# PCB-BI8-3x5C3_V2.net
KiCad netlist of a schematic drawn in EAGLE
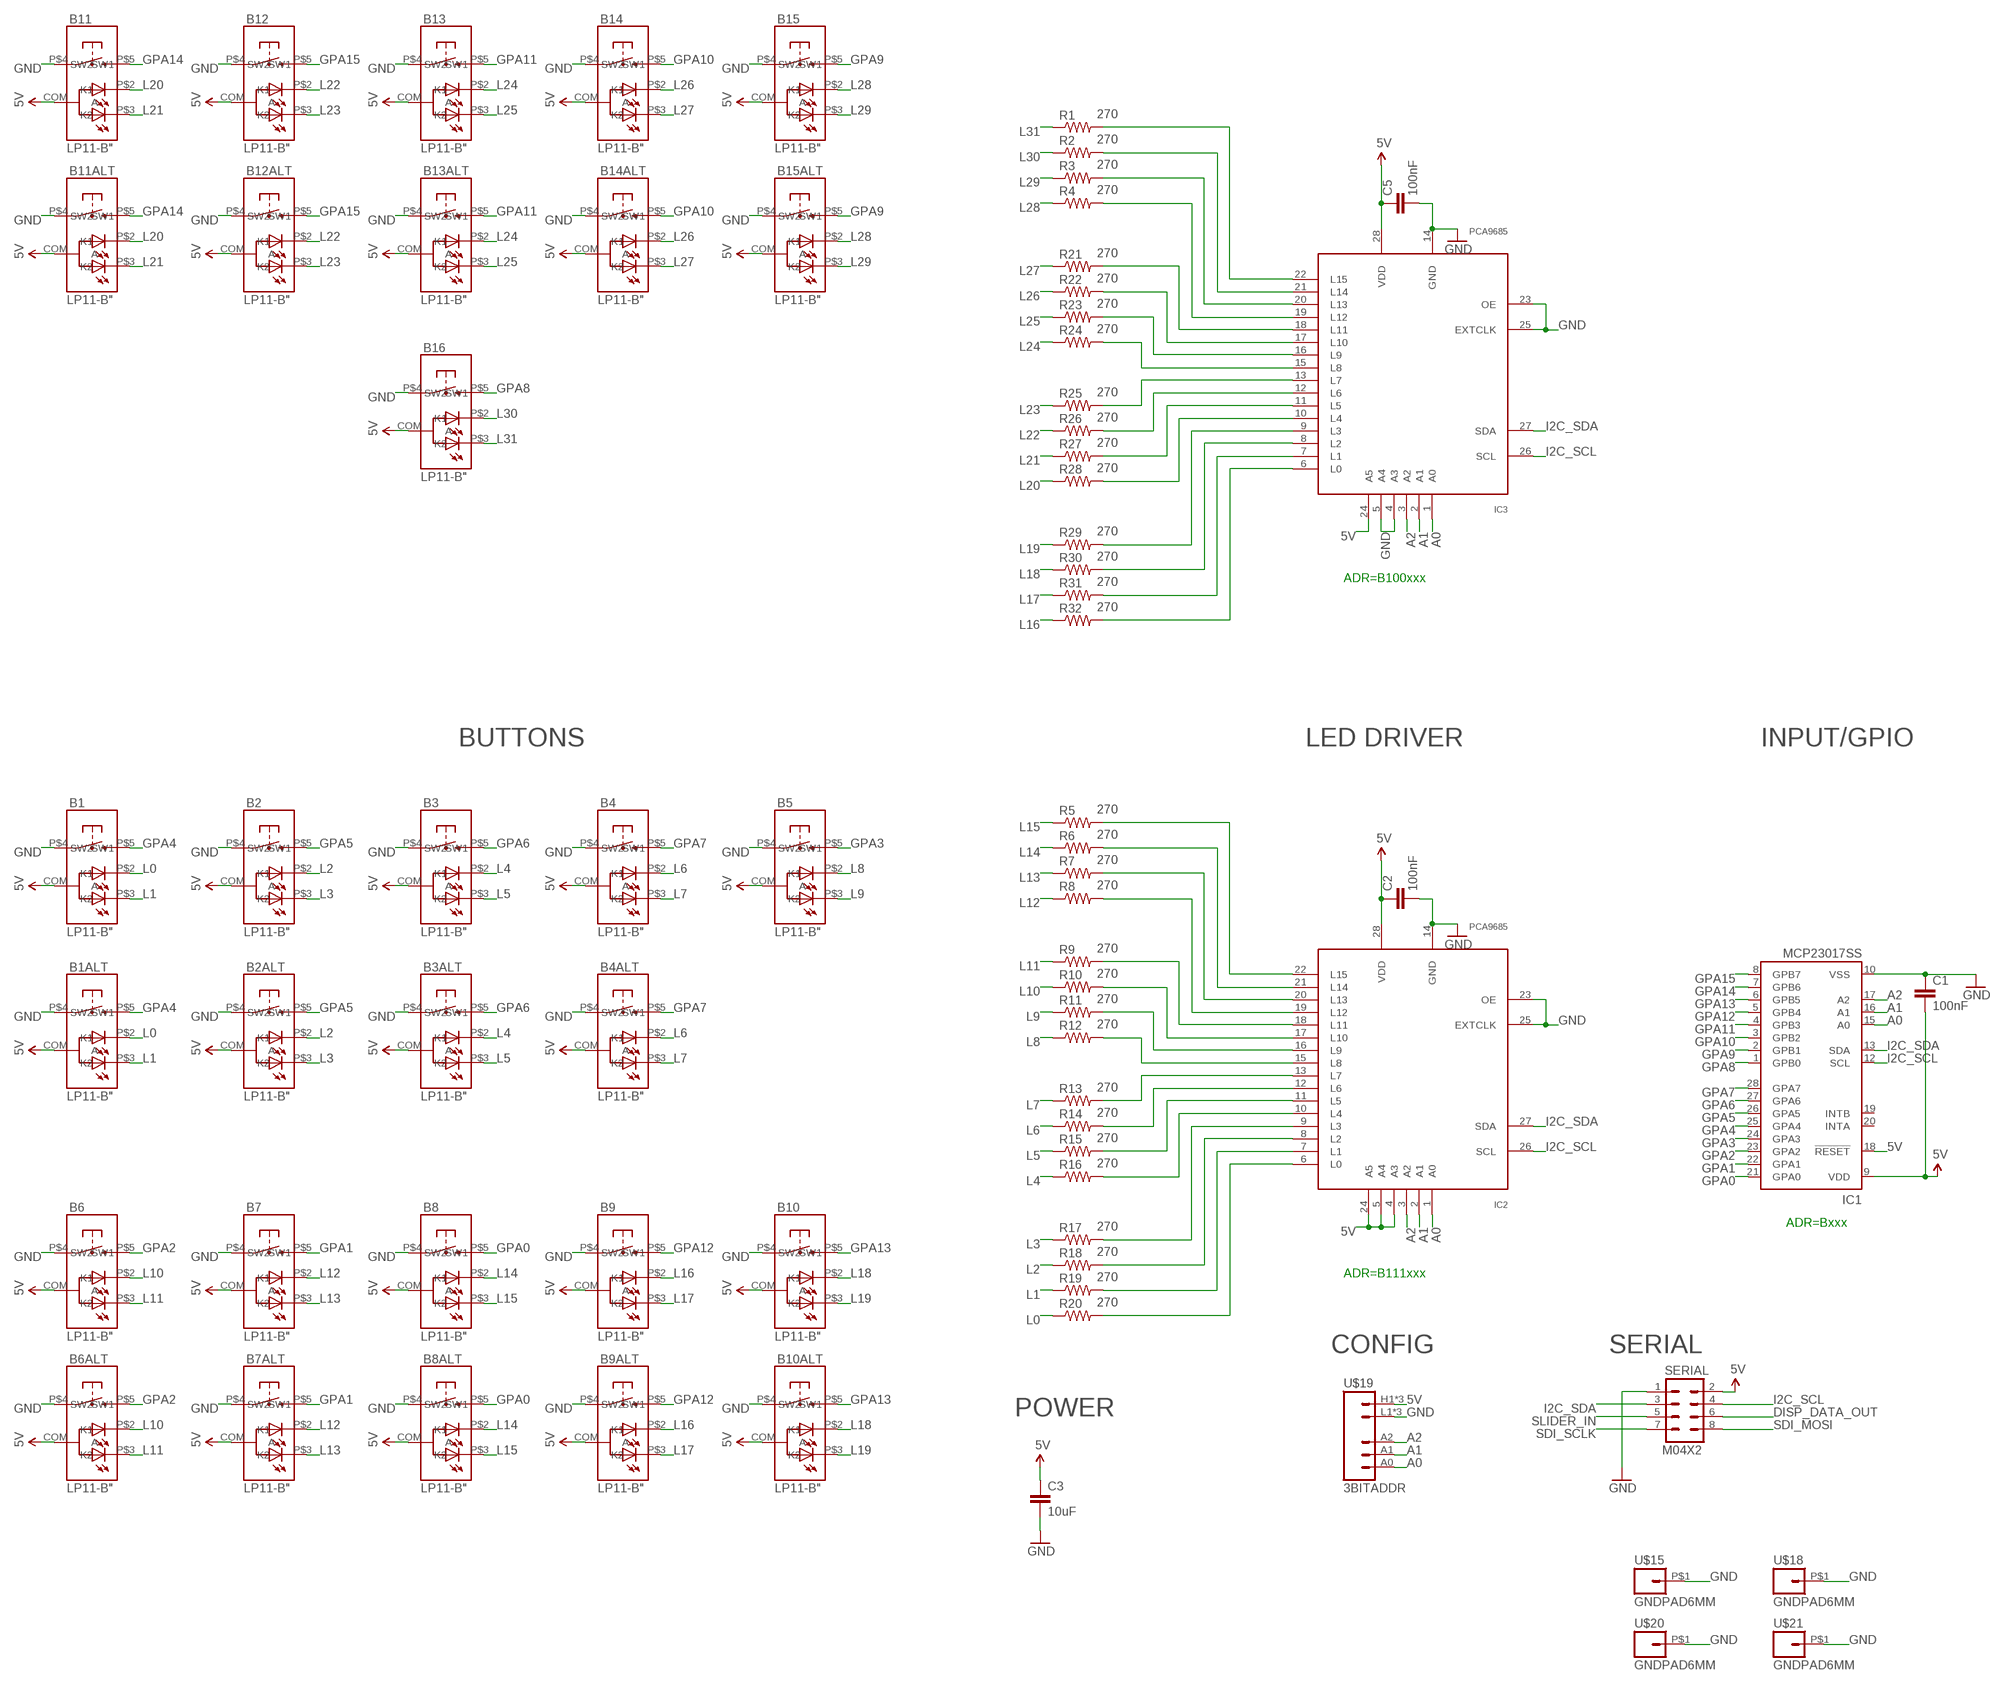
[diagram p0: schematic, sheet 1]

(export (version "E")
  (design (tool "Eeschema 10.0.6"))
  (components
    (comp (ref "B1")
      (value "LP11-B\"")
      (footprint "eagle-import:LP11")
      (libsource (lib "eagle-import") (part "LP11-B{dblquote}"))
    )
    (comp (ref "B1ALT")
      (value "LP11-B\"")
      (footprint "eagle-import:LP11")
      (libsource (lib "eagle-import") (part "LP11-B{dblquote}"))
    )
    (comp (ref "B2")
      (value "LP11-B\"")
      (footprint "eagle-import:LP11")
      (libsource (lib "eagle-import") (part "LP11-B{dblquote}"))
    )
    (comp (ref "B2ALT")
      (value "LP11-B\"")
      (footprint "eagle-import:LP11")
      (libsource (lib "eagle-import") (part "LP11-B{dblquote}"))
    )
    (comp (ref "B3")
      (value "LP11-B\"")
      (footprint "eagle-import:LP11")
      (libsource (lib "eagle-import") (part "LP11-B{dblquote}"))
    )
    (comp (ref "B3ALT")
      (value "LP11-B\"")
      (footprint "eagle-import:LP11")
      (libsource (lib "eagle-import") (part "LP11-B{dblquote}"))
    )
    (comp (ref "B4")
      (value "LP11-B\"")
      (footprint "eagle-import:LP11")
      (libsource (lib "eagle-import") (part "LP11-B{dblquote}"))
    )
    (comp (ref "B4ALT")
      (value "LP11-B\"")
      (footprint "eagle-import:LP11")
      (libsource (lib "eagle-import") (part "LP11-B{dblquote}"))
    )
    (comp (ref "B5")
      (value "LP11-B\"")
      (footprint "eagle-import:LP11")
      (libsource (lib "eagle-import") (part "LP11-B{dblquote}"))
    )
    (comp (ref "B6")
      (value "LP11-B\"")
      (footprint "eagle-import:LP11")
      (libsource (lib "eagle-import") (part "LP11-B{dblquote}"))
    )
    (comp (ref "B6ALT")
      (value "LP11-B\"")
      (footprint "eagle-import:LP11")
      (libsource (lib "eagle-import") (part "LP11-B{dblquote}"))
    )
    (comp (ref "B7")
      (value "LP11-B\"")
      (footprint "eagle-import:LP11")
      (libsource (lib "eagle-import") (part "LP11-B{dblquote}"))
    )
    (comp (ref "B7ALT")
      (value "LP11-B\"")
      (footprint "eagle-import:LP11")
      (libsource (lib "eagle-import") (part "LP11-B{dblquote}"))
    )
    (comp (ref "B8")
      (value "LP11-B\"")
      (footprint "eagle-import:LP11")
      (libsource (lib "eagle-import") (part "LP11-B{dblquote}"))
    )
    (comp (ref "B8ALT")
      (value "LP11-B\"")
      (footprint "eagle-import:LP11")
      (libsource (lib "eagle-import") (part "LP11-B{dblquote}"))
    )
    (comp (ref "B9")
      (value "LP11-B\"")
      (footprint "eagle-import:LP11")
      (libsource (lib "eagle-import") (part "LP11-B{dblquote}"))
    )
    (comp (ref "B9ALT")
      (value "LP11-B\"")
      (footprint "eagle-import:LP11")
      (libsource (lib "eagle-import") (part "LP11-B{dblquote}"))
    )
    (comp (ref "B10")
      (value "LP11-B\"")
      (footprint "eagle-import:LP11")
      (libsource (lib "eagle-import") (part "LP11-B{dblquote}"))
    )
    (comp (ref "B10ALT")
      (value "LP11-B\"")
      (footprint "eagle-import:LP11")
      (libsource (lib "eagle-import") (part "LP11-B{dblquote}"))
    )
    (comp (ref "B11")
      (value "LP11-B\"")
      (footprint "eagle-import:LP11")
      (libsource (lib "eagle-import") (part "LP11-B{dblquote}"))
    )
    (comp (ref "B11ALT")
      (value "LP11-B\"")
      (footprint "eagle-import:LP11")
      (libsource (lib "eagle-import") (part "LP11-B{dblquote}"))
    )
    (comp (ref "B12")
      (value "LP11-B\"")
      (footprint "eagle-import:LP11")
      (libsource (lib "eagle-import") (part "LP11-B{dblquote}"))
    )
    (comp (ref "B12ALT")
      (value "LP11-B\"")
      (footprint "eagle-import:LP11")
      (libsource (lib "eagle-import") (part "LP11-B{dblquote}"))
    )
    (comp (ref "B13")
      (value "LP11-B\"")
      (footprint "eagle-import:LP11")
      (libsource (lib "eagle-import") (part "LP11-B{dblquote}"))
    )
    (comp (ref "B13ALT")
      (value "LP11-B\"")
      (footprint "eagle-import:LP11")
      (libsource (lib "eagle-import") (part "LP11-B{dblquote}"))
    )
    (comp (ref "B14")
      (value "LP11-B\"")
      (footprint "eagle-import:LP11")
      (libsource (lib "eagle-import") (part "LP11-B{dblquote}"))
    )
    (comp (ref "B14ALT")
      (value "LP11-B\"")
      (footprint "eagle-import:LP11")
      (libsource (lib "eagle-import") (part "LP11-B{dblquote}"))
    )
    (comp (ref "B15")
      (value "LP11-B\"")
      (footprint "eagle-import:LP11")
      (libsource (lib "eagle-import") (part "LP11-B{dblquote}"))
    )
    (comp (ref "B15ALT")
      (value "LP11-B\"")
      (footprint "eagle-import:LP11")
      (libsource (lib "eagle-import") (part "LP11-B{dblquote}"))
    )
    (comp (ref "B16")
      (value "LP11-B\"")
      (footprint "eagle-import:LP11")
      (libsource (lib "eagle-import") (part "LP11-B{dblquote}"))
    )
    (comp (ref "C1")
      (value "100nF")
      (footprint "eagle-import:0603-CAP")
      (libsource (lib "eagle-import") (part "CAP0603-CAP"))
    )
    (comp (ref "C2")
      (value "100nF")
      (footprint "eagle-import:0603-CAP")
      (libsource (lib "eagle-import") (part "CAP0603-CAP"))
    )
    (comp (ref "C3")
      (value "10uF")
      (footprint "eagle-import:0805")
      (libsource (lib "eagle-import") (part "CAP0805"))
    )
    (comp (ref "C5")
      (value "100nF")
      (footprint "eagle-import:0603-CAP")
      (libsource (lib "eagle-import") (part "CAP0603-CAP"))
    )
    (comp (ref "IC1")
      (value "MCP23017SS")
      (footprint "eagle-import:SSOP28")
      (fields
        (field (name "MF") "MICROCHIP")
        (field (name "MPN") "MCP23017-E/SS")
        (field (name "MPN_1") "MCP23017-E/SS")
        (field (name "OC_FARNELL") "1467674")
        (field (name "OC_NEWARK") "31K2960")
      )
      (libsource (lib "eagle-import") (part "MCP23017SS"))
    )
    (comp (ref "IC2")
      (value "PCA9685")
      (footprint "eagle-import:TSSOP28")
      (libsource (lib "eagle-import") (part "PCA9685"))
    )
    (comp (ref "IC3")
      (value "PCA9685")
      (footprint "eagle-import:TSSOP28")
      (libsource (lib "eagle-import") (part "PCA9685"))
    )
    (comp (ref "R1")
      (value "270")
      (footprint "eagle-import:0603-RES")
      (libsource (lib "eagle-import") (part "RESISTOR0603-RES"))
    )
    (comp (ref "R2")
      (value "270")
      (footprint "eagle-import:0603-RES")
      (libsource (lib "eagle-import") (part "RESISTOR0603-RES"))
    )
    (comp (ref "R3")
      (value "270")
      (footprint "eagle-import:0603-RES")
      (libsource (lib "eagle-import") (part "RESISTOR0603-RES"))
    )
    (comp (ref "R4")
      (value "270")
      (footprint "eagle-import:0603-RES")
      (libsource (lib "eagle-import") (part "RESISTOR0603-RES"))
    )
    (comp (ref "R5")
      (value "270")
      (footprint "eagle-import:0603-RES")
      (libsource (lib "eagle-import") (part "RESISTOR0603-RES"))
    )
    (comp (ref "R6")
      (value "270")
      (footprint "eagle-import:0603-RES")
      (libsource (lib "eagle-import") (part "RESISTOR0603-RES"))
    )
    (comp (ref "R7")
      (value "270")
      (footprint "eagle-import:0603-RES")
      (libsource (lib "eagle-import") (part "RESISTOR0603-RES"))
    )
    (comp (ref "R8")
      (value "270")
      (footprint "eagle-import:0603-RES")
      (libsource (lib "eagle-import") (part "RESISTOR0603-RES"))
    )
    (comp (ref "R9")
      (value "270")
      (footprint "eagle-import:0603-RES")
      (libsource (lib "eagle-import") (part "RESISTOR0603-RES"))
    )
    (comp (ref "R10")
      (value "270")
      (footprint "eagle-import:0603-RES")
      (libsource (lib "eagle-import") (part "RESISTOR0603-RES"))
    )
    (comp (ref "R11")
      (value "270")
      (footprint "eagle-import:0603-RES")
      (libsource (lib "eagle-import") (part "RESISTOR0603-RES"))
    )
    (comp (ref "R12")
      (value "270")
      (footprint "eagle-import:0603-RES")
      (libsource (lib "eagle-import") (part "RESISTOR0603-RES"))
    )
    (comp (ref "R13")
      (value "270")
      (footprint "eagle-import:0603-RES")
      (libsource (lib "eagle-import") (part "RESISTOR0603-RES"))
    )
    (comp (ref "R14")
      (value "270")
      (footprint "eagle-import:0603-RES")
      (libsource (lib "eagle-import") (part "RESISTOR0603-RES"))
    )
    (comp (ref "R15")
      (value "270")
      (footprint "eagle-import:0603-RES")
      (libsource (lib "eagle-import") (part "RESISTOR0603-RES"))
    )
    (comp (ref "R16")
      (value "270")
      (footprint "eagle-import:0603-RES")
      (libsource (lib "eagle-import") (part "RESISTOR0603-RES"))
    )
    (comp (ref "R17")
      (value "270")
      (footprint "eagle-import:0603-RES")
      (libsource (lib "eagle-import") (part "RESISTOR0603-RES"))
    )
    (comp (ref "R18")
      (value "270")
      (footprint "eagle-import:0603-RES")
      (libsource (lib "eagle-import") (part "RESISTOR0603-RES"))
    )
    (comp (ref "R19")
      (value "270")
      (footprint "eagle-import:0603-RES")
      (libsource (lib "eagle-import") (part "RESISTOR0603-RES"))
    )
    (comp (ref "R20")
      (value "270")
      (footprint "eagle-import:0603-RES")
      (libsource (lib "eagle-import") (part "RESISTOR0603-RES"))
    )
    (comp (ref "R21")
      (value "270")
      (footprint "eagle-import:0603-RES")
      (libsource (lib "eagle-import") (part "RESISTOR0603-RES"))
    )
    (comp (ref "R22")
      (value "270")
      (footprint "eagle-import:0603-RES")
      (libsource (lib "eagle-import") (part "RESISTOR0603-RES"))
    )
    (comp (ref "R23")
      (value "270")
      (footprint "eagle-import:0603-RES")
      (libsource (lib "eagle-import") (part "RESISTOR0603-RES"))
    )
    (comp (ref "R24")
      (value "270")
      (footprint "eagle-import:0603-RES")
      (libsource (lib "eagle-import") (part "RESISTOR0603-RES"))
    )
    (comp (ref "R25")
      (value "270")
      (footprint "eagle-import:0603-RES")
      (libsource (lib "eagle-import") (part "RESISTOR0603-RES"))
    )
    (comp (ref "R26")
      (value "270")
      (footprint "eagle-import:0603-RES")
      (libsource (lib "eagle-import") (part "RESISTOR0603-RES"))
    )
    (comp (ref "R27")
      (value "270")
      (footprint "eagle-import:0603-RES")
      (libsource (lib "eagle-import") (part "RESISTOR0603-RES"))
    )
    (comp (ref "R28")
      (value "270")
      (footprint "eagle-import:0603-RES")
      (libsource (lib "eagle-import") (part "RESISTOR0603-RES"))
    )
    (comp (ref "R29")
      (value "270")
      (footprint "eagle-import:0603-RES")
      (libsource (lib "eagle-import") (part "RESISTOR0603-RES"))
    )
    (comp (ref "R30")
      (value "270")
      (footprint "eagle-import:0603-RES")
      (libsource (lib "eagle-import") (part "RESISTOR0603-RES"))
    )
    (comp (ref "R31")
      (value "270")
      (footprint "eagle-import:0603-RES")
      (libsource (lib "eagle-import") (part "RESISTOR0603-RES"))
    )
    (comp (ref "R32")
      (value "270")
      (footprint "eagle-import:0603-RES")
      (libsource (lib "eagle-import") (part "RESISTOR0603-RES"))
    )
    (comp (ref "SERIAL")
      (value "M04X2")
      (footprint "eagle-import:2X4")
      (libsource (lib "eagle-import") (part "M04X2"))
    )
    (comp (ref "U$15")
      (value "GNDPAD6MM")
      (footprint "eagle-import:3.2MMPAD6MM")
      (libsource (lib "eagle-import") (part "GNDPAD6MM"))
    )
    (comp (ref "U$18")
      (value "GNDPAD6MM")
      (footprint "eagle-import:3.2MMPAD6MM")
      (libsource (lib "eagle-import") (part "GNDPAD6MM"))
    )
    (comp (ref "U$19")
      (value "3BITADDR")
      (footprint "eagle-import:3BITADDR")
      (libsource (lib "eagle-import") (part "3BITADDR"))
    )
    (comp (ref "U$20")
      (value "GNDPAD6MM")
      (footprint "eagle-import:3.2MMPAD6MM")
      (libsource (lib "eagle-import") (part "GNDPAD6MM"))
    )
    (comp (ref "U$21")
      (value "GNDPAD6MM")
      (footprint "eagle-import:3.2MMPAD6MM")
      (libsource (lib "eagle-import") (part "GNDPAD6MM"))
    )
  )
  (nets
    (net (code "1") (name "5V") (class "Default")
      (node (ref "B1") (pin "COM") (pinfunction "A_COM") (pintype "bidirectional"))
      (node (ref "B10") (pin "COM") (pinfunction "A_COM") (pintype "bidirectional"))
      (node (ref "B10ALT") (pin "COM") (pinfunction "A_COM") (pintype "bidirectional"))
      (node (ref "B11") (pin "COM") (pinfunction "A_COM") (pintype "bidirectional"))
      (node (ref "B11ALT") (pin "COM") (pinfunction "A_COM") (pintype "bidirectional"))
      (node (ref "B12") (pin "COM") (pinfunction "A_COM") (pintype "bidirectional"))
      (node (ref "B12ALT") (pin "COM") (pinfunction "A_COM") (pintype "bidirectional"))
      (node (ref "B13") (pin "COM") (pinfunction "A_COM") (pintype "bidirectional"))
      (node (ref "B13ALT") (pin "COM") (pinfunction "A_COM") (pintype "bidirectional"))
      (node (ref "B14") (pin "COM") (pinfunction "A_COM") (pintype "bidirectional"))
      (node (ref "B14ALT") (pin "COM") (pinfunction "A_COM") (pintype "bidirectional"))
      (node (ref "B15") (pin "COM") (pinfunction "A_COM") (pintype "bidirectional"))
      (node (ref "B15ALT") (pin "COM") (pinfunction "A_COM") (pintype "bidirectional"))
      (node (ref "B16") (pin "COM") (pinfunction "A_COM") (pintype "bidirectional"))
      (node (ref "B1ALT") (pin "COM") (pinfunction "A_COM") (pintype "bidirectional"))
      (node (ref "B2") (pin "COM") (pinfunction "A_COM") (pintype "bidirectional"))
      (node (ref "B2ALT") (pin "COM") (pinfunction "A_COM") (pintype "bidirectional"))
      (node (ref "B3") (pin "COM") (pinfunction "A_COM") (pintype "bidirectional"))
      (node (ref "B3ALT") (pin "COM") (pinfunction "A_COM") (pintype "bidirectional"))
      (node (ref "B4") (pin "COM") (pinfunction "A_COM") (pintype "bidirectional"))
      (node (ref "B4ALT") (pin "COM") (pinfunction "A_COM") (pintype "bidirectional"))
      (node (ref "B5") (pin "COM") (pinfunction "A_COM") (pintype "bidirectional"))
      (node (ref "B6") (pin "COM") (pinfunction "A_COM") (pintype "bidirectional"))
      (node (ref "B6ALT") (pin "COM") (pinfunction "A_COM") (pintype "bidirectional"))
      (node (ref "B7") (pin "COM") (pinfunction "A_COM") (pintype "bidirectional"))
      (node (ref "B7ALT") (pin "COM") (pinfunction "A_COM") (pintype "bidirectional"))
      (node (ref "B8") (pin "COM") (pinfunction "A_COM") (pintype "bidirectional"))
      (node (ref "B8ALT") (pin "COM") (pinfunction "A_COM") (pintype "bidirectional"))
      (node (ref "B9") (pin "COM") (pinfunction "A_COM") (pintype "bidirectional"))
      (node (ref "B9ALT") (pin "COM") (pinfunction "A_COM") (pintype "bidirectional"))
      (node (ref "C1") (pin "2") (pinfunction "2_2") (pintype "passive"))
      (node (ref "C2") (pin "1") (pinfunction "1_1") (pintype "passive"))
      (node (ref "C3") (pin "1") (pinfunction "1_1") (pintype "passive"))
      (node (ref "C5") (pin "1") (pinfunction "1_1") (pintype "passive"))
      (node (ref "IC1") (pin "18") (pinfunction "~{RESET}_18") (pintype "input"))
      (node (ref "IC1") (pin "9") (pinfunction "VDD_9") (pintype "power_in"))
      (node (ref "IC2") (pin "24") (pinfunction "A5_24") (pintype "input"))
      (node (ref "IC2") (pin "28") (pinfunction "VDD_28") (pintype "power_in"))
      (node (ref "IC2") (pin "4") (pinfunction "A3_4") (pintype "input"))
      (node (ref "IC2") (pin "5") (pinfunction "A4_5") (pintype "input"))
      (node (ref "IC3") (pin "24") (pinfunction "A5_24") (pintype "input"))
      (node (ref "IC3") (pin "28") (pinfunction "VDD_28") (pintype "power_in"))
      (node (ref "SERIAL") (pin "2") (pinfunction "2_2") (pintype "passive"))
      (node (ref "U$19") (pin "H1") (pinfunction "VCC_H1") (pintype "passive"))
      (node (ref "U$19") (pin "H2") (pinfunction "VCC_H2") (pintype "passive"))
      (node (ref "U$19") (pin "H3") (pinfunction "VCC_H3") (pintype "passive"))
    )
    (net (code "2") (name "A0") (class "Default")
      (node (ref "IC1") (pin "15") (pinfunction "A0_15") (pintype "input"))
      (node (ref "IC2") (pin "1") (pinfunction "A0_1") (pintype "input"))
      (node (ref "IC3") (pin "1") (pinfunction "A0_1") (pintype "input"))
      (node (ref "U$19") (pin "A0") (pinfunction "A0_A0") (pintype "passive"))
    )
    (net (code "3") (name "A1") (class "Default")
      (node (ref "IC1") (pin "16") (pinfunction "A1_16") (pintype "input"))
      (node (ref "IC2") (pin "2") (pinfunction "A1_2") (pintype "input"))
      (node (ref "IC3") (pin "2") (pinfunction "A1_2") (pintype "input"))
      (node (ref "U$19") (pin "A1") (pinfunction "A1_A1") (pintype "passive"))
    )
    (net (code "4") (name "A2") (class "Default")
      (node (ref "IC1") (pin "17") (pinfunction "A2_17") (pintype "input"))
      (node (ref "IC2") (pin "3") (pinfunction "A2_3") (pintype "input"))
      (node (ref "IC3") (pin "3") (pinfunction "A2_3") (pintype "input"))
      (node (ref "U$19") (pin "A2") (pinfunction "A2_A2") (pintype "passive"))
    )
    (net (code "5") (name "DISP_DATA_OUT") (class "Default")
      (node (ref "SERIAL") (pin "6") (pinfunction "6_6") (pintype "passive"))
    )
    (net (code "6") (name "GND") (class "Default")
      (node (ref "B1") (pin "P$4") (pinfunction "SW1_P$4") (pintype "bidirectional"))
      (node (ref "B10") (pin "P$4") (pinfunction "SW1_P$4") (pintype "bidirectional"))
      (node (ref "B10ALT") (pin "P$4") (pinfunction "SW1_P$4") (pintype "bidirectional"))
      (node (ref "B11") (pin "P$4") (pinfunction "SW1_P$4") (pintype "bidirectional"))
      (node (ref "B11ALT") (pin "P$4") (pinfunction "SW1_P$4") (pintype "bidirectional"))
      (node (ref "B12") (pin "P$4") (pinfunction "SW1_P$4") (pintype "bidirectional"))
      (node (ref "B12ALT") (pin "P$4") (pinfunction "SW1_P$4") (pintype "bidirectional"))
      (node (ref "B13") (pin "P$4") (pinfunction "SW1_P$4") (pintype "bidirectional"))
      (node (ref "B13ALT") (pin "P$4") (pinfunction "SW1_P$4") (pintype "bidirectional"))
      (node (ref "B14") (pin "P$4") (pinfunction "SW1_P$4") (pintype "bidirectional"))
      (node (ref "B14ALT") (pin "P$4") (pinfunction "SW1_P$4") (pintype "bidirectional"))
      (node (ref "B15") (pin "P$4") (pinfunction "SW1_P$4") (pintype "bidirectional"))
      (node (ref "B15ALT") (pin "P$4") (pinfunction "SW1_P$4") (pintype "bidirectional"))
      (node (ref "B16") (pin "P$4") (pinfunction "SW1_P$4") (pintype "bidirectional"))
      (node (ref "B1ALT") (pin "P$4") (pinfunction "SW1_P$4") (pintype "bidirectional"))
      (node (ref "B2") (pin "P$4") (pinfunction "SW1_P$4") (pintype "bidirectional"))
      (node (ref "B2ALT") (pin "P$4") (pinfunction "SW1_P$4") (pintype "bidirectional"))
      (node (ref "B3") (pin "P$4") (pinfunction "SW1_P$4") (pintype "bidirectional"))
      (node (ref "B3ALT") (pin "P$4") (pinfunction "SW1_P$4") (pintype "bidirectional"))
      (node (ref "B4") (pin "P$4") (pinfunction "SW1_P$4") (pintype "bidirectional"))
      (node (ref "B4ALT") (pin "P$4") (pinfunction "SW1_P$4") (pintype "bidirectional"))
      (node (ref "B5") (pin "P$4") (pinfunction "SW1_P$4") (pintype "bidirectional"))
      (node (ref "B6") (pin "P$4") (pinfunction "SW1_P$4") (pintype "bidirectional"))
      (node (ref "B6ALT") (pin "P$4") (pinfunction "SW1_P$4") (pintype "bidirectional"))
      (node (ref "B7") (pin "P$4") (pinfunction "SW1_P$4") (pintype "bidirectional"))
      (node (ref "B7ALT") (pin "P$4") (pinfunction "SW1_P$4") (pintype "bidirectional"))
      (node (ref "B8") (pin "P$4") (pinfunction "SW1_P$4") (pintype "bidirectional"))
      (node (ref "B8ALT") (pin "P$4") (pinfunction "SW1_P$4") (pintype "bidirectional"))
      (node (ref "B9") (pin "P$4") (pinfunction "SW1_P$4") (pintype "bidirectional"))
      (node (ref "B9ALT") (pin "P$4") (pinfunction "SW1_P$4") (pintype "bidirectional"))
      (node (ref "C1") (pin "1") (pinfunction "1_1") (pintype "passive"))
      (node (ref "C2") (pin "2") (pinfunction "2_2") (pintype "passive"))
      (node (ref "C3") (pin "2") (pinfunction "2_2") (pintype "passive"))
      (node (ref "C5") (pin "2") (pinfunction "2_2") (pintype "passive"))
      (node (ref "IC1") (pin "10") (pinfunction "VSS_10") (pintype "power_in"))
      (node (ref "IC2") (pin "14") (pinfunction "GND_14") (pintype "power_in"))
      (node (ref "IC2") (pin "23") (pinfunction "OE_23") (pintype "input"))
      (node (ref "IC2") (pin "25") (pinfunction "EXTCLK_25") (pintype "input"))
      (node (ref "IC3") (pin "14") (pinfunction "GND_14") (pintype "power_in"))
      (node (ref "IC3") (pin "23") (pinfunction "OE_23") (pintype "input"))
      (node (ref "IC3") (pin "25") (pinfunction "EXTCLK_25") (pintype "input"))
      (node (ref "IC3") (pin "4") (pinfunction "A3_4") (pintype "input"))
      (node (ref "IC3") (pin "5") (pinfunction "A4_5") (pintype "input"))
      (node (ref "SERIAL") (pin "1") (pinfunction "1_1") (pintype "passive"))
      (node (ref "U$15") (pin "P$1") (pinfunction "1_P$1") (pintype "passive"))
      (node (ref "U$18") (pin "P$1") (pinfunction "1_P$1") (pintype "passive"))
      (node (ref "U$19") (pin "L1") (pinfunction "GND_L1") (pintype "passive"))
      (node (ref "U$19") (pin "L2") (pinfunction "GND_L2") (pintype "passive"))
      (node (ref "U$19") (pin "L3") (pinfunction "GND_L3") (pintype "passive"))
      (node (ref "U$20") (pin "P$1") (pinfunction "1_P$1") (pintype "passive"))
      (node (ref "U$21") (pin "P$1") (pinfunction "1_P$1") (pintype "passive"))
    )
    (net (code "7") (name "GPA0") (class "Default")
      (node (ref "B8") (pin "P$5") (pinfunction "SW2_P$5") (pintype "bidirectional"))
      (node (ref "B8ALT") (pin "P$5") (pinfunction "SW2_P$5") (pintype "bidirectional"))
      (node (ref "IC1") (pin "21") (pinfunction "GPA0_21") (pintype "bidirectional"))
    )
    (net (code "8") (name "GPA1") (class "Default")
      (node (ref "B7") (pin "P$5") (pinfunction "SW2_P$5") (pintype "bidirectional"))
      (node (ref "B7ALT") (pin "P$5") (pinfunction "SW2_P$5") (pintype "bidirectional"))
      (node (ref "IC1") (pin "22") (pinfunction "GPA1_22") (pintype "bidirectional"))
    )
    (net (code "9") (name "GPA2") (class "Default")
      (node (ref "B6") (pin "P$5") (pinfunction "SW2_P$5") (pintype "bidirectional"))
      (node (ref "B6ALT") (pin "P$5") (pinfunction "SW2_P$5") (pintype "bidirectional"))
      (node (ref "IC1") (pin "23") (pinfunction "GPA2_23") (pintype "bidirectional"))
    )
    (net (code "10") (name "GPA3") (class "Default")
      (node (ref "B5") (pin "P$5") (pinfunction "SW2_P$5") (pintype "bidirectional"))
      (node (ref "IC1") (pin "24") (pinfunction "GPA3_24") (pintype "bidirectional"))
    )
    (net (code "11") (name "GPA4") (class "Default")
      (node (ref "B1") (pin "P$5") (pinfunction "SW2_P$5") (pintype "bidirectional"))
      (node (ref "B1ALT") (pin "P$5") (pinfunction "SW2_P$5") (pintype "bidirectional"))
      (node (ref "IC1") (pin "25") (pinfunction "GPA4_25") (pintype "bidirectional"))
    )
    (net (code "12") (name "GPA5") (class "Default")
      (node (ref "B2") (pin "P$5") (pinfunction "SW2_P$5") (pintype "bidirectional"))
      (node (ref "B2ALT") (pin "P$5") (pinfunction "SW2_P$5") (pintype "bidirectional"))
      (node (ref "IC1") (pin "26") (pinfunction "GPA5_26") (pintype "bidirectional"))
    )
    (net (code "13") (name "GPA6") (class "Default")
      (node (ref "B3") (pin "P$5") (pinfunction "SW2_P$5") (pintype "bidirectional"))
      (node (ref "B3ALT") (pin "P$5") (pinfunction "SW2_P$5") (pintype "bidirectional"))
      (node (ref "IC1") (pin "27") (pinfunction "GPA6_27") (pintype "bidirectional"))
    )
    (net (code "14") (name "GPA7") (class "Default")
      (node (ref "B4") (pin "P$5") (pinfunction "SW2_P$5") (pintype "bidirectional"))
      (node (ref "B4ALT") (pin "P$5") (pinfunction "SW2_P$5") (pintype "bidirectional"))
      (node (ref "IC1") (pin "28") (pinfunction "GPA7_28") (pintype "bidirectional"))
    )
    (net (code "15") (name "GPA8") (class "Default")
      (node (ref "B16") (pin "P$5") (pinfunction "SW2_P$5") (pintype "bidirectional"))
      (node (ref "IC1") (pin "1") (pinfunction "GPB0_1") (pintype "bidirectional"))
    )
    (net (code "16") (name "GPA9") (class "Default")
      (node (ref "B15") (pin "P$5") (pinfunction "SW2_P$5") (pintype "bidirectional"))
      (node (ref "B15ALT") (pin "P$5") (pinfunction "SW2_P$5") (pintype "bidirectional"))
      (node (ref "IC1") (pin "2") (pinfunction "GPB1_2") (pintype "bidirectional"))
    )
    (net (code "17") (name "GPA10") (class "Default")
      (node (ref "B14") (pin "P$5") (pinfunction "SW2_P$5") (pintype "bidirectional"))
      (node (ref "B14ALT") (pin "P$5") (pinfunction "SW2_P$5") (pintype "bidirectional"))
      (node (ref "IC1") (pin "3") (pinfunction "GPB2_3") (pintype "bidirectional"))
    )
    (net (code "18") (name "GPA11") (class "Default")
      (node (ref "B13") (pin "P$5") (pinfunction "SW2_P$5") (pintype "bidirectional"))
      (node (ref "B13ALT") (pin "P$5") (pinfunction "SW2_P$5") (pintype "bidirectional"))
      (node (ref "IC1") (pin "4") (pinfunction "GPB3_4") (pintype "bidirectional"))
    )
    (net (code "19") (name "GPA12") (class "Default")
      (node (ref "B9") (pin "P$5") (pinfunction "SW2_P$5") (pintype "bidirectional"))
      (node (ref "B9ALT") (pin "P$5") (pinfunction "SW2_P$5") (pintype "bidirectional"))
      (node (ref "IC1") (pin "5") (pinfunction "GPB4_5") (pintype "bidirectional"))
    )
    (net (code "20") (name "GPA13") (class "Default")
      (node (ref "B10") (pin "P$5") (pinfunction "SW2_P$5") (pintype "bidirectional"))
      (node (ref "B10ALT") (pin "P$5") (pinfunction "SW2_P$5") (pintype "bidirectional"))
      (node (ref "IC1") (pin "6") (pinfunction "GPB5_6") (pintype "bidirectional"))
    )
    (net (code "21") (name "GPA14") (class "Default")
      (node (ref "B11") (pin "P$5") (pinfunction "SW2_P$5") (pintype "bidirectional"))
      (node (ref "B11ALT") (pin "P$5") (pinfunction "SW2_P$5") (pintype "bidirectional"))
      (node (ref "IC1") (pin "7") (pinfunction "GPB6_7") (pintype "bidirectional"))
    )
    (net (code "22") (name "GPA15") (class "Default")
      (node (ref "B12") (pin "P$5") (pinfunction "SW2_P$5") (pintype "bidirectional"))
      (node (ref "B12ALT") (pin "P$5") (pinfunction "SW2_P$5") (pintype "bidirectional"))
      (node (ref "IC1") (pin "8") (pinfunction "GPB7_8") (pintype "bidirectional"))
    )
    (net (code "23") (name "I2C_SCL") (class "Default")
      (node (ref "IC1") (pin "12") (pinfunction "SCL_12") (pintype "input"))
      (node (ref "IC2") (pin "26") (pinfunction "SCL_26") (pintype "input"))
      (node (ref "IC3") (pin "26") (pinfunction "SCL_26") (pintype "input"))
      (node (ref "SERIAL") (pin "4") (pinfunction "4_4") (pintype "passive"))
    )
    (net (code "24") (name "I2C_SDA") (class "Default")
      (node (ref "IC1") (pin "13") (pinfunction "SDA_13") (pintype "bidirectional"))
      (node (ref "IC2") (pin "27") (pinfunction "SDA_27") (pintype "input"))
      (node (ref "IC3") (pin "27") (pinfunction "SDA_27") (pintype "input"))
      (node (ref "SERIAL") (pin "3") (pinfunction "3_3") (pintype "passive"))
    )
    (net (code "25") (name "L0") (class "Default")
      (node (ref "B1") (pin "P$2") (pinfunction "K1_P$2") (pintype "bidirectional"))
      (node (ref "B1ALT") (pin "P$2") (pinfunction "K1_P$2") (pintype "bidirectional"))
      (node (ref "R20") (pin "1") (pinfunction "1_1") (pintype "passive"))
    )
    (net (code "26") (name "L1") (class "Default")
      (node (ref "B1") (pin "P$3") (pinfunction "K2_P$3") (pintype "bidirectional"))
      (node (ref "B1ALT") (pin "P$3") (pinfunction "K2_P$3") (pintype "bidirectional"))
      (node (ref "R19") (pin "1") (pinfunction "1_1") (pintype "passive"))
    )
    (net (code "27") (name "L2") (class "Default")
      (node (ref "B2") (pin "P$2") (pinfunction "K1_P$2") (pintype "bidirectional"))
      (node (ref "B2ALT") (pin "P$2") (pinfunction "K1_P$2") (pintype "bidirectional"))
      (node (ref "R18") (pin "1") (pinfunction "1_1") (pintype "passive"))
    )
    (net (code "28") (name "L3") (class "Default")
      (node (ref "B2") (pin "P$3") (pinfunction "K2_P$3") (pintype "bidirectional"))
      (node (ref "B2ALT") (pin "P$3") (pinfunction "K2_P$3") (pintype "bidirectional"))
      (node (ref "R17") (pin "1") (pinfunction "1_1") (pintype "passive"))
    )
    (net (code "29") (name "L4") (class "Default")
      (node (ref "B3") (pin "P$2") (pinfunction "K1_P$2") (pintype "bidirectional"))
      (node (ref "B3ALT") (pin "P$2") (pinfunction "K1_P$2") (pintype "bidirectional"))
      (node (ref "R16") (pin "1") (pinfunction "1_1") (pintype "passive"))
    )
    (net (code "30") (name "L5") (class "Default")
      (node (ref "B3") (pin "P$3") (pinfunction "K2_P$3") (pintype "bidirectional"))
      (node (ref "B3ALT") (pin "P$3") (pinfunction "K2_P$3") (pintype "bidirectional"))
      (node (ref "R15") (pin "1") (pinfunction "1_1") (pintype "passive"))
    )
    (net (code "31") (name "L6") (class "Default")
      (node (ref "B4") (pin "P$2") (pinfunction "K1_P$2") (pintype "bidirectional"))
      (node (ref "B4ALT") (pin "P$2") (pinfunction "K1_P$2") (pintype "bidirectional"))
      (node (ref "R14") (pin "1") (pinfunction "1_1") (pintype "passive"))
    )
    (net (code "32") (name "L7") (class "Default")
      (node (ref "B4") (pin "P$3") (pinfunction "K2_P$3") (pintype "bidirectional"))
      (node (ref "B4ALT") (pin "P$3") (pinfunction "K2_P$3") (pintype "bidirectional"))
      (node (ref "R13") (pin "1") (pinfunction "1_1") (pintype "passive"))
    )
    (net (code "33") (name "L8") (class "Default")
      (node (ref "B5") (pin "P$2") (pinfunction "K1_P$2") (pintype "bidirectional"))
      (node (ref "R12") (pin "1") (pinfunction "1_1") (pintype "passive"))
    )
    (net (code "34") (name "L9") (class "Default")
      (node (ref "B5") (pin "P$3") (pinfunction "K2_P$3") (pintype "bidirectional"))
      (node (ref "R11") (pin "1") (pinfunction "1_1") (pintype "passive"))
    )
    (net (code "35") (name "L10") (class "Default")
      (node (ref "B6") (pin "P$2") (pinfunction "K1_P$2") (pintype "bidirectional"))
      (node (ref "B6ALT") (pin "P$2") (pinfunction "K1_P$2") (pintype "bidirectional"))
      (node (ref "R10") (pin "1") (pinfunction "1_1") (pintype "passive"))
    )
    (net (code "36") (name "L11") (class "Default")
      (node (ref "B6") (pin "P$3") (pinfunction "K2_P$3") (pintype "bidirectional"))
      (node (ref "B6ALT") (pin "P$3") (pinfunction "K2_P$3") (pintype "bidirectional"))
      (node (ref "R9") (pin "1") (pinfunction "1_1") (pintype "passive"))
    )
    (net (code "37") (name "L12") (class "Default")
      (node (ref "B7") (pin "P$2") (pinfunction "K1_P$2") (pintype "bidirectional"))
      (node (ref "B7ALT") (pin "P$2") (pinfunction "K1_P$2") (pintype "bidirectional"))
      (node (ref "R8") (pin "1") (pinfunction "1_1") (pintype "passive"))
    )
    (net (code "38") (name "L13") (class "Default")
      (node (ref "B7") (pin "P$3") (pinfunction "K2_P$3") (pintype "bidirectional"))
      (node (ref "B7ALT") (pin "P$3") (pinfunction "K2_P$3") (pintype "bidirectional"))
      (node (ref "R7") (pin "1") (pinfunction "1_1") (pintype "passive"))
    )
    (net (code "39") (name "L14") (class "Default")
      (node (ref "B8") (pin "P$2") (pinfunction "K1_P$2") (pintype "bidirectional"))
      (node (ref "B8ALT") (pin "P$2") (pinfunction "K1_P$2") (pintype "bidirectional"))
      (node (ref "R6") (pin "1") (pinfunction "1_1") (pintype "passive"))
    )
    (net (code "40") (name "L15") (class "Default")
      (node (ref "B8") (pin "P$3") (pinfunction "K2_P$3") (pintype "bidirectional"))
      (node (ref "B8ALT") (pin "P$3") (pinfunction "K2_P$3") (pintype "bidirectional"))
      (node (ref "R5") (pin "1") (pinfunction "1_1") (pintype "passive"))
    )
    (net (code "41") (name "L16") (class "Default")
      (node (ref "B9") (pin "P$2") (pinfunction "K1_P$2") (pintype "bidirectional"))
      (node (ref "B9ALT") (pin "P$2") (pinfunction "K1_P$2") (pintype "bidirectional"))
      (node (ref "R32") (pin "1") (pinfunction "1_1") (pintype "passive"))
    )
    (net (code "42") (name "L17") (class "Default")
      (node (ref "B9") (pin "P$3") (pinfunction "K2_P$3") (pintype "bidirectional"))
      (node (ref "B9ALT") (pin "P$3") (pinfunction "K2_P$3") (pintype "bidirectional"))
      (node (ref "R31") (pin "1") (pinfunction "1_1") (pintype "passive"))
    )
    (net (code "43") (name "L18") (class "Default")
      (node (ref "B10") (pin "P$2") (pinfunction "K1_P$2") (pintype "bidirectional"))
      (node (ref "B10ALT") (pin "P$2") (pinfunction "K1_P$2") (pintype "bidirectional"))
      (node (ref "R30") (pin "1") (pinfunction "1_1") (pintype "passive"))
    )
    (net (code "44") (name "L19") (class "Default")
      (node (ref "B10") (pin "P$3") (pinfunction "K2_P$3") (pintype "bidirectional"))
      (node (ref "B10ALT") (pin "P$3") (pinfunction "K2_P$3") (pintype "bidirectional"))
      (node (ref "R29") (pin "1") (pinfunction "1_1") (pintype "passive"))
    )
    (net (code "45") (name "L20") (class "Default")
      (node (ref "B11") (pin "P$2") (pinfunction "K1_P$2") (pintype "bidirectional"))
      (node (ref "B11ALT") (pin "P$2") (pinfunction "K1_P$2") (pintype "bidirectional"))
      (node (ref "R28") (pin "1") (pinfunction "1_1") (pintype "passive"))
    )
    (net (code "46") (name "L21") (class "Default")
      (node (ref "B11") (pin "P$3") (pinfunction "K2_P$3") (pintype "bidirectional"))
      (node (ref "B11ALT") (pin "P$3") (pinfunction "K2_P$3") (pintype "bidirectional"))
      (node (ref "R27") (pin "1") (pinfunction "1_1") (pintype "passive"))
    )
    (net (code "47") (name "L22") (class "Default")
      (node (ref "B12") (pin "P$2") (pinfunction "K1_P$2") (pintype "bidirectional"))
      (node (ref "B12ALT") (pin "P$2") (pinfunction "K1_P$2") (pintype "bidirectional"))
      (node (ref "R26") (pin "1") (pinfunction "1_1") (pintype "passive"))
    )
    (net (code "48") (name "L23") (class "Default")
      (node (ref "B12") (pin "P$3") (pinfunction "K2_P$3") (pintype "bidirectional"))
      (node (ref "B12ALT") (pin "P$3") (pinfunction "K2_P$3") (pintype "bidirectional"))
      (node (ref "R25") (pin "1") (pinfunction "1_1") (pintype "passive"))
    )
    (net (code "49") (name "L24") (class "Default")
      (node (ref "B13") (pin "P$2") (pinfunction "K1_P$2") (pintype "bidirectional"))
      (node (ref "B13ALT") (pin "P$2") (pinfunction "K1_P$2") (pintype "bidirectional"))
      (node (ref "R24") (pin "1") (pinfunction "1_1") (pintype "passive"))
    )
    (net (code "50") (name "L25") (class "Default")
      (node (ref "B13") (pin "P$3") (pinfunction "K2_P$3") (pintype "bidirectional"))
      (node (ref "B13ALT") (pin "P$3") (pinfunction "K2_P$3") (pintype "bidirectional"))
      (node (ref "R23") (pin "1") (pinfunction "1_1") (pintype "passive"))
    )
    (net (code "51") (name "L26") (class "Default")
      (node (ref "B14") (pin "P$2") (pinfunction "K1_P$2") (pintype "bidirectional"))
      (node (ref "B14ALT") (pin "P$2") (pinfunction "K1_P$2") (pintype "bidirectional"))
      (node (ref "R22") (pin "1") (pinfunction "1_1") (pintype "passive"))
    )
    (net (code "52") (name "L27") (class "Default")
      (node (ref "B14") (pin "P$3") (pinfunction "K2_P$3") (pintype "bidirectional"))
      (node (ref "B14ALT") (pin "P$3") (pinfunction "K2_P$3") (pintype "bidirectional"))
      (node (ref "R21") (pin "1") (pinfunction "1_1") (pintype "passive"))
    )
    (net (code "53") (name "L28") (class "Default")
      (node (ref "B15") (pin "P$2") (pinfunction "K1_P$2") (pintype "bidirectional"))
      (node (ref "B15ALT") (pin "P$2") (pinfunction "K1_P$2") (pintype "bidirectional"))
      (node (ref "R4") (pin "1") (pinfunction "1_1") (pintype "passive"))
    )
    (net (code "54") (name "L29") (class "Default")
      (node (ref "B15") (pin "P$3") (pinfunction "K2_P$3") (pintype "bidirectional"))
      (node (ref "B15ALT") (pin "P$3") (pinfunction "K2_P$3") (pintype "bidirectional"))
      (node (ref "R3") (pin "1") (pinfunction "1_1") (pintype "passive"))
    )
    (net (code "55") (name "L30") (class "Default")
      (node (ref "B16") (pin "P$2") (pinfunction "K1_P$2") (pintype "bidirectional"))
      (node (ref "R2") (pin "1") (pinfunction "1_1") (pintype "passive"))
    )
    (net (code "56") (name "L31") (class "Default")
      (node (ref "B16") (pin "P$3") (pinfunction "K2_P$3") (pintype "bidirectional"))
      (node (ref "R1") (pin "1") (pinfunction "1_1") (pintype "passive"))
    )
    (net (code "57") (name "Net-(IC2-L0)") (class "Default")
      (node (ref "IC2") (pin "6") (pinfunction "L0_6") (pintype "output"))
      (node (ref "R20") (pin "2") (pinfunction "2_2") (pintype "passive"))
    )
    (net (code "58") (name "Net-(IC2-L1)") (class "Default")
      (node (ref "IC2") (pin "7") (pinfunction "L1_7") (pintype "output"))
      (node (ref "R19") (pin "2") (pinfunction "2_2") (pintype "passive"))
    )
    (net (code "59") (name "Net-(IC2-L2)") (class "Default")
      (node (ref "IC2") (pin "8") (pinfunction "L2_8") (pintype "output"))
      (node (ref "R18") (pin "2") (pinfunction "2_2") (pintype "passive"))
    )
    (net (code "60") (name "Net-(IC2-L3)") (class "Default")
      (node (ref "IC2") (pin "9") (pinfunction "L3_9") (pintype "output"))
      (node (ref "R17") (pin "2") (pinfunction "2_2") (pintype "passive"))
    )
    (net (code "61") (name "Net-(IC2-L4)") (class "Default")
      (node (ref "IC2") (pin "10") (pinfunction "L4_10") (pintype "output"))
      (node (ref "R16") (pin "2") (pinfunction "2_2") (pintype "passive"))
    )
    (net (code "62") (name "Net-(IC2-L5)") (class "Default")
      (node (ref "IC2") (pin "11") (pinfunction "L5_11") (pintype "output"))
      (node (ref "R15") (pin "2") (pinfunction "2_2") (pintype "passive"))
    )
    (net (code "63") (name "Net-(IC2-L6)") (class "Default")
      (node (ref "IC2") (pin "12") (pinfunction "L6_12") (pintype "output"))
      (node (ref "R14") (pin "2") (pinfunction "2_2") (pintype "passive"))
    )
    (net (code "64") (name "Net-(IC2-L7)") (class "Default")
      (node (ref "IC2") (pin "13") (pinfunction "L7_13") (pintype "output"))
      (node (ref "R13") (pin "2") (pinfunction "2_2") (pintype "passive"))
    )
    (net (code "65") (name "Net-(IC2-L8)") (class "Default")
      (node (ref "IC2") (pin "15") (pinfunction "L8_15") (pintype "output"))
      (node (ref "R12") (pin "2") (pinfunction "2_2") (pintype "passive"))
    )
    (net (code "66") (name "Net-(IC2-L9)") (class "Default")
      (node (ref "IC2") (pin "16") (pinfunction "L9_16") (pintype "output"))
      (node (ref "R11") (pin "2") (pinfunction "2_2") (pintype "passive"))
    )
    (net (code "67") (name "Net-(IC2-L10)") (class "Default")
      (node (ref "IC2") (pin "17") (pinfunction "L10_17") (pintype "output"))
      (node (ref "R10") (pin "2") (pinfunction "2_2") (pintype "passive"))
    )
    (net (code "68") (name "Net-(IC2-L11)") (class "Default")
      (node (ref "IC2") (pin "18") (pinfunction "L11_18") (pintype "output"))
      (node (ref "R9") (pin "2") (pinfunction "2_2") (pintype "passive"))
    )
    (net (code "69") (name "Net-(IC2-L12)") (class "Default")
      (node (ref "IC2") (pin "19") (pinfunction "L12_19") (pintype "output"))
      (node (ref "R8") (pin "2") (pinfunction "2_2") (pintype "passive"))
    )
    (net (code "70") (name "Net-(IC2-L13)") (class "Default")
      (node (ref "IC2") (pin "20") (pinfunction "L13_20") (pintype "output"))
      (node (ref "R7") (pin "2") (pinfunction "2_2") (pintype "passive"))
    )
    (net (code "71") (name "Net-(IC2-L14)") (class "Default")
      (node (ref "IC2") (pin "21") (pinfunction "L14_21") (pintype "output"))
      (node (ref "R6") (pin "2") (pinfunction "2_2") (pintype "passive"))
    )
    (net (code "72") (name "Net-(IC2-L15)") (class "Default")
      (node (ref "IC2") (pin "22") (pinfunction "L15_22") (pintype "output"))
      (node (ref "R5") (pin "2") (pinfunction "2_2") (pintype "passive"))
    )
    (net (code "73") (name "Net-(IC3-L0)") (class "Default")
      (node (ref "IC3") (pin "6") (pinfunction "L0_6") (pintype "output"))
      (node (ref "R32") (pin "2") (pinfunction "2_2") (pintype "passive"))
    )
    (net (code "74") (name "Net-(IC3-L1)") (class "Default")
      (node (ref "IC3") (pin "7") (pinfunction "L1_7") (pintype "output"))
      (node (ref "R31") (pin "2") (pinfunction "2_2") (pintype "passive"))
    )
    (net (code "75") (name "Net-(IC3-L2)") (class "Default")
      (node (ref "IC3") (pin "8") (pinfunction "L2_8") (pintype "output"))
      (node (ref "R30") (pin "2") (pinfunction "2_2") (pintype "passive"))
    )
    (net (code "76") (name "Net-(IC3-L3)") (class "Default")
      (node (ref "IC3") (pin "9") (pinfunction "L3_9") (pintype "output"))
      (node (ref "R29") (pin "2") (pinfunction "2_2") (pintype "passive"))
    )
    (net (code "77") (name "Net-(IC3-L4)") (class "Default")
      (node (ref "IC3") (pin "10") (pinfunction "L4_10") (pintype "output"))
      (node (ref "R28") (pin "2") (pinfunction "2_2") (pintype "passive"))
    )
    (net (code "78") (name "Net-(IC3-L5)") (class "Default")
      (node (ref "IC3") (pin "11") (pinfunction "L5_11") (pintype "output"))
      (node (ref "R27") (pin "2") (pinfunction "2_2") (pintype "passive"))
    )
    (net (code "79") (name "Net-(IC3-L6)") (class "Default")
      (node (ref "IC3") (pin "12") (pinfunction "L6_12") (pintype "output"))
      (node (ref "R26") (pin "2") (pinfunction "2_2") (pintype "passive"))
    )
    (net (code "80") (name "Net-(IC3-L7)") (class "Default")
      (node (ref "IC3") (pin "13") (pinfunction "L7_13") (pintype "output"))
      (node (ref "R25") (pin "2") (pinfunction "2_2") (pintype "passive"))
    )
    (net (code "81") (name "Net-(IC3-L8)") (class "Default")
      (node (ref "IC3") (pin "15") (pinfunction "L8_15") (pintype "output"))
      (node (ref "R24") (pin "2") (pinfunction "2_2") (pintype "passive"))
    )
    (net (code "82") (name "Net-(IC3-L9)") (class "Default")
      (node (ref "IC3") (pin "16") (pinfunction "L9_16") (pintype "output"))
      (node (ref "R23") (pin "2") (pinfunction "2_2") (pintype "passive"))
    )
    (net (code "83") (name "Net-(IC3-L10)") (class "Default")
      (node (ref "IC3") (pin "17") (pinfunction "L10_17") (pintype "output"))
      (node (ref "R22") (pin "2") (pinfunction "2_2") (pintype "passive"))
    )
    (net (code "84") (name "Net-(IC3-L11)") (class "Default")
      (node (ref "IC3") (pin "18") (pinfunction "L11_18") (pintype "output"))
      (node (ref "R21") (pin "2") (pinfunction "2_2") (pintype "passive"))
    )
    (net (code "85") (name "Net-(IC3-L12)") (class "Default")
      (node (ref "IC3") (pin "19") (pinfunction "L12_19") (pintype "output"))
      (node (ref "R4") (pin "2") (pinfunction "2_2") (pintype "passive"))
    )
    (net (code "86") (name "Net-(IC3-L13)") (class "Default")
      (node (ref "IC3") (pin "20") (pinfunction "L13_20") (pintype "output"))
      (node (ref "R3") (pin "2") (pinfunction "2_2") (pintype "passive"))
    )
    (net (code "87") (name "Net-(IC3-L14)") (class "Default")
      (node (ref "IC3") (pin "21") (pinfunction "L14_21") (pintype "output"))
      (node (ref "R2") (pin "2") (pinfunction "2_2") (pintype "passive"))
    )
    (net (code "88") (name "Net-(IC3-L15)") (class "Default")
      (node (ref "IC3") (pin "22") (pinfunction "L15_22") (pintype "output"))
      (node (ref "R1") (pin "2") (pinfunction "2_2") (pintype "passive"))
    )
    (net (code "89") (name "SDI_MOSI") (class "Default")
      (node (ref "SERIAL") (pin "8") (pinfunction "8_8") (pintype "passive"))
    )
    (net (code "90") (name "SDI_SCLK") (class "Default")
      (node (ref "SERIAL") (pin "7") (pinfunction "7_7") (pintype "passive"))
    )
    (net (code "91") (name "SLIDER_IN") (class "Default")
      (node (ref "SERIAL") (pin "5") (pinfunction "5_5") (pintype "passive"))
    )
    (net (code "92") (name "unconnected-(IC1-INTA-Pad20)") (class "Default")
      (node (ref "IC1") (pin "20") (pinfunction "INTA_20") (pintype "output"))
    )
    (net (code "93") (name "unconnected-(IC1-INTB-Pad19)") (class "Default")
      (node (ref "IC1") (pin "19") (pinfunction "INTB_19") (pintype "output"))
    )
  )
)
